# esp32_breakout.net
KiCad netlist of a schematic drawn in Altium Designer
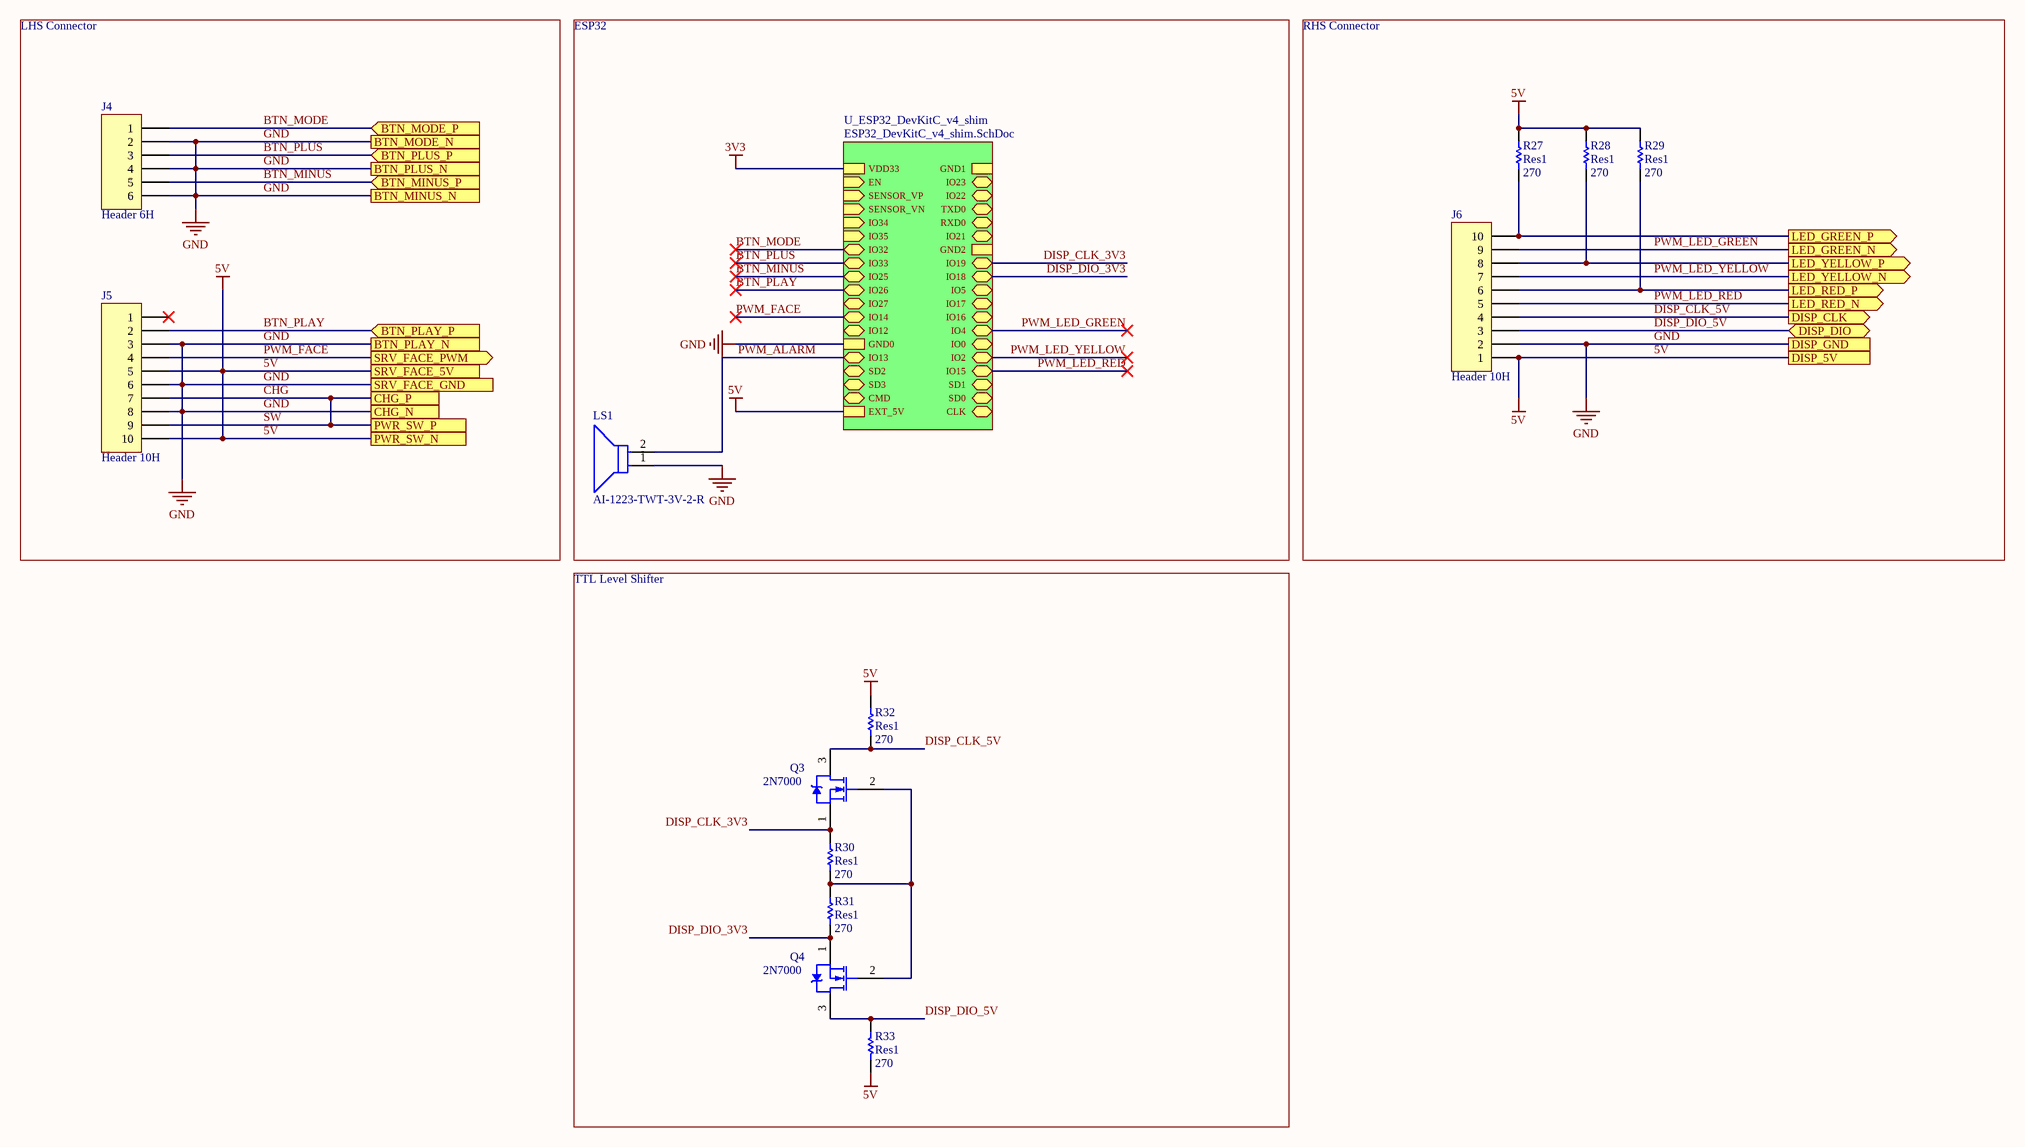
[diagram p0: esp32_breakout.SchDoc]

(export (version "E")
  (design (tool "Eeschema 10.0.6"))
  (components
    (comp (ref "J4")
      (value "Header 6H")
      (footprint "HDR1X6H")
      (description "Header, 6-Pin, Right Angle")
      (fields (field (name "PUBLISHER") "Altium Limited"))
      (libsource (lib "Miscellaneous Connectors") (part "Header 6H"))
    )
    (comp (ref "J5")
      (value "Header 10H")
      (footprint "HDR1X10H")
      (description "Header, 10-Pin, Right Angle")
      (fields (field (name "PUBLISHER") "Altium Limited"))
      (libsource (lib "") (part "Header 10H_1"))
    )
    (comp (ref "J6")
      (value "Header 10H")
      (footprint "HDR1X10H")
      (description "Header, 10-Pin, Right Angle")
      (fields (field (name "PUBLISHER") "Altium Limited"))
      (libsource (lib "Miscellaneous Connectors") (part "Header 10H"))
    )
    (comp (ref "LS1")
      (value "AI-1223-TWT-3V-2-R")
      (footprint "FP-AI-1223-TWT-3V-2-R-MFG")
      (description "BUZZER MAGNETIC 3V 12MM TH")
      (libsource (lib "Altium Content Vault") (part "1973c4b650225fd2ddacaff6b763965"))
    )
    (comp (ref "Q3")
      (value "2N7000")
      (footprint "ONSC-TO-92-3-29-11")
      (description "Small Signal MOSFET, 200 mA, 60 V, N-Channel, 3-Pin TO-92, Bulk Box")
      (fields (field (name "MANUFACTURER") "On Semiconductor"))
      (libsource (lib "Altium Content Vault") (part "ONSC-NMOS-S1G2D3-3"))
    )
    (comp (ref "Q4")
      (value "2N7000")
      (footprint "ONSC-TO-92-3-29-11")
      (description "Small Signal MOSFET, 200 mA, 60 V, N-Channel, 3-Pin TO-92, Bulk Box")
      (fields (field (name "MANUFACTURER") "On Semiconductor"))
      (libsource (lib "Altium Content Vault") (part "ONSC-NMOS-S1G2D3-3"))
    )
    (comp (ref "R27")
      (value "Res1")
      (footprint "AXIAL-0.3")
      (description "Resistor")
      (fields (field (name "ALTIUM_VALUE") "270") (field (name "PUBLISHER") "Altium Limited"))
      (libsource (lib "Miscellaneous Devices") (part "Res1"))
    )
    (comp (ref "R28")
      (value "Res1")
      (footprint "AXIAL-0.3")
      (description "Resistor")
      (fields (field (name "ALTIUM_VALUE") "270") (field (name "PUBLISHER") "Altium Limited"))
      (libsource (lib "Miscellaneous Devices") (part "Res1"))
    )
    (comp (ref "R29")
      (value "Res1")
      (footprint "AXIAL-0.3")
      (description "Resistor")
      (fields (field (name "ALTIUM_VALUE") "270") (field (name "PUBLISHER") "Altium Limited"))
      (libsource (lib "Miscellaneous Devices") (part "Res1"))
    )
    (comp (ref "R30")
      (value "Res1")
      (footprint "AXIAL-0.3")
      (description "Resistor")
      (fields (field (name "ALTIUM_VALUE") "270") (field (name "PUBLISHER") "Altium Limited"))
      (libsource (lib "Miscellaneous Devices") (part "Res1"))
    )
    (comp (ref "R31")
      (value "Res1")
      (footprint "AXIAL-0.3")
      (description "Resistor")
      (fields (field (name "ALTIUM_VALUE") "270") (field (name "PUBLISHER") "Altium Limited"))
      (libsource (lib "Miscellaneous Devices") (part "Res1"))
    )
    (comp (ref "R32")
      (value "Res1")
      (footprint "AXIAL-0.3")
      (description "Resistor")
      (fields (field (name "ALTIUM_VALUE") "270") (field (name "PUBLISHER") "Altium Limited"))
      (libsource (lib "Miscellaneous Devices") (part "Res1"))
    )
    (comp (ref "R33")
      (value "Res1")
      (footprint "AXIAL-0.3")
      (description "Resistor")
      (fields (field (name "ALTIUM_VALUE") "270") (field (name "PUBLISHER") "Altium Limited"))
      (libsource (lib "Miscellaneous Devices") (part "Res1"))
    )
  )
  (nets
    (net (code "1") (name "/BTN_MINUS") (class "Default")
      (node (ref "J4") (pin "5") (pinfunction "5_5") (pintype "passive"))
    )
    (net (code "2") (name "/BTN_MODE") (class "Default")
      (node (ref "J4") (pin "1") (pinfunction "1_1") (pintype "passive"))
    )
    (net (code "3") (name "/BTN_PLAY") (class "Default")
      (node (ref "J5") (pin "2") (pinfunction "2_2") (pintype "passive"))
    )
    (net (code "4") (name "/BTN_PLUS") (class "Default")
      (node (ref "J4") (pin "3") (pinfunction "3_3") (pintype "passive"))
    )
    (net (code "5") (name "/CHG") (class "Default")
      (node (ref "J5") (pin "7") (pinfunction "7_7") (pintype "passive"))
      (node (ref "J5") (pin "9") (pinfunction "9_9") (pintype "passive"))
    )
    (net (code "8") (name "/DISP_CLK_3V3") (class "Default")
      (node (ref "Q3") (pin "1") (pinfunction "S_1") (pintype "passive"))
      (node (ref "R30") (pin "2") (pinfunction "2_2") (pintype "passive"))
    )
    (net (code "9") (name "/DISP_CLK_5V") (class "Default")
      (node (ref "J6") (pin "4") (pinfunction "4_4") (pintype "passive"))
      (node (ref "Q3") (pin "3") (pinfunction "D_3") (pintype "passive"))
      (node (ref "R32") (pin "1") (pinfunction "1_1") (pintype "passive"))
    )
    (net (code "10") (name "/DISP_DIO_3V3") (class "Default")
      (node (ref "Q4") (pin "1") (pinfunction "S_1") (pintype "passive"))
      (node (ref "R31") (pin "1") (pinfunction "1_1") (pintype "passive"))
    )
    (net (code "11") (name "/DISP_DIO_5V") (class "Default")
      (node (ref "J6") (pin "3") (pinfunction "3_3") (pintype "passive"))
      (node (ref "Q4") (pin "3") (pinfunction "D_3") (pintype "passive"))
      (node (ref "R33") (pin "1") (pinfunction "1_1") (pintype "passive"))
    )
    (net (code "26") (name "/LED_GREEN_P") (class "Default")
      (node (ref "J6") (pin "10") (pinfunction "10_10") (pintype "passive"))
      (node (ref "R27") (pin "1") (pinfunction "1_1") (pintype "passive"))
    )
    (net (code "27") (name "/LED_RED_P") (class "Default")
      (node (ref "J6") (pin "6") (pinfunction "6_6") (pintype "passive"))
      (node (ref "R29") (pin "1") (pinfunction "1_1") (pintype "passive"))
    )
    (net (code "28") (name "/LED_YELLOW_P") (class "Default")
      (node (ref "J6") (pin "8") (pinfunction "8_8") (pintype "passive"))
      (node (ref "R28") (pin "1") (pinfunction "1_1") (pintype "passive"))
    )
    (net (code "29") (name "/PWM_ALARM") (class "Default")
      (node (ref "LS1") (pin "2") (pinfunction "A_2") (pintype "passive"))
    )
    (net (code "30") (name "/PWM_FACE") (class "Default")
      (node (ref "J5") (pin "4") (pinfunction "4_4") (pintype "passive"))
    )
    (net (code "31") (name "/PWM_LED_GREEN") (class "Default")
      (node (ref "J6") (pin "9") (pinfunction "9_9") (pintype "passive+no_connect"))
    )
    (net (code "32") (name "/PWM_LED_RED") (class "Default")
      (node (ref "J6") (pin "5") (pinfunction "5_5") (pintype "passive+no_connect"))
    )
    (net (code "33") (name "/PWM_LED_YELLOW") (class "Default")
      (node (ref "J6") (pin "7") (pinfunction "7_7") (pintype "passive+no_connect"))
    )
    (net (code "43") (name "5V") (class "Default")
      (node (ref "J5") (pin "10") (pinfunction "10_10") (pintype "passive"))
      (node (ref "J5") (pin "5") (pinfunction "5_5") (pintype "passive"))
      (node (ref "J6") (pin "1") (pinfunction "1_1") (pintype "passive"))
      (node (ref "R27") (pin "2") (pinfunction "2_2") (pintype "passive"))
      (node (ref "R28") (pin "2") (pinfunction "2_2") (pintype "passive"))
      (node (ref "R29") (pin "2") (pinfunction "2_2") (pintype "passive"))
      (node (ref "R32") (pin "2") (pinfunction "2_2") (pintype "passive"))
      (node (ref "R33") (pin "2") (pinfunction "2_2") (pintype "passive"))
    )
    (net (code "44") (name "GND") (class "Default")
      (node (ref "J4") (pin "2") (pinfunction "2_2") (pintype "passive"))
      (node (ref "J4") (pin "4") (pinfunction "4_4") (pintype "passive"))
      (node (ref "J4") (pin "6") (pinfunction "6_6") (pintype "passive"))
      (node (ref "J5") (pin "3") (pinfunction "3_3") (pintype "passive"))
      (node (ref "J5") (pin "6") (pinfunction "6_6") (pintype "passive"))
      (node (ref "J5") (pin "8") (pinfunction "8_8") (pintype "passive"))
      (node (ref "J6") (pin "2") (pinfunction "2_2") (pintype "passive"))
      (node (ref "LS1") (pin "1") (pinfunction "C_1") (pintype "passive"))
    )
    (net (code "45") (name "Net-(Q3-G)") (class "Default")
      (node (ref "Q3") (pin "2") (pinfunction "G_2") (pintype "passive"))
      (node (ref "Q4") (pin "2") (pinfunction "G_2") (pintype "passive"))
      (node (ref "R30") (pin "1") (pinfunction "1_1") (pintype "passive"))
      (node (ref "R31") (pin "2") (pinfunction "2_2") (pintype "passive"))
    )
    (net (code "46") (name "unconnected-(J5-Pad1)") (class "Default")
      (node (ref "J5") (pin "1") (pinfunction "1_1") (pintype "passive+no_connect"))
    )
  )
)
